# ig-normal2ver2.net
KiCad netlist of a schematic drawn in EAGLE
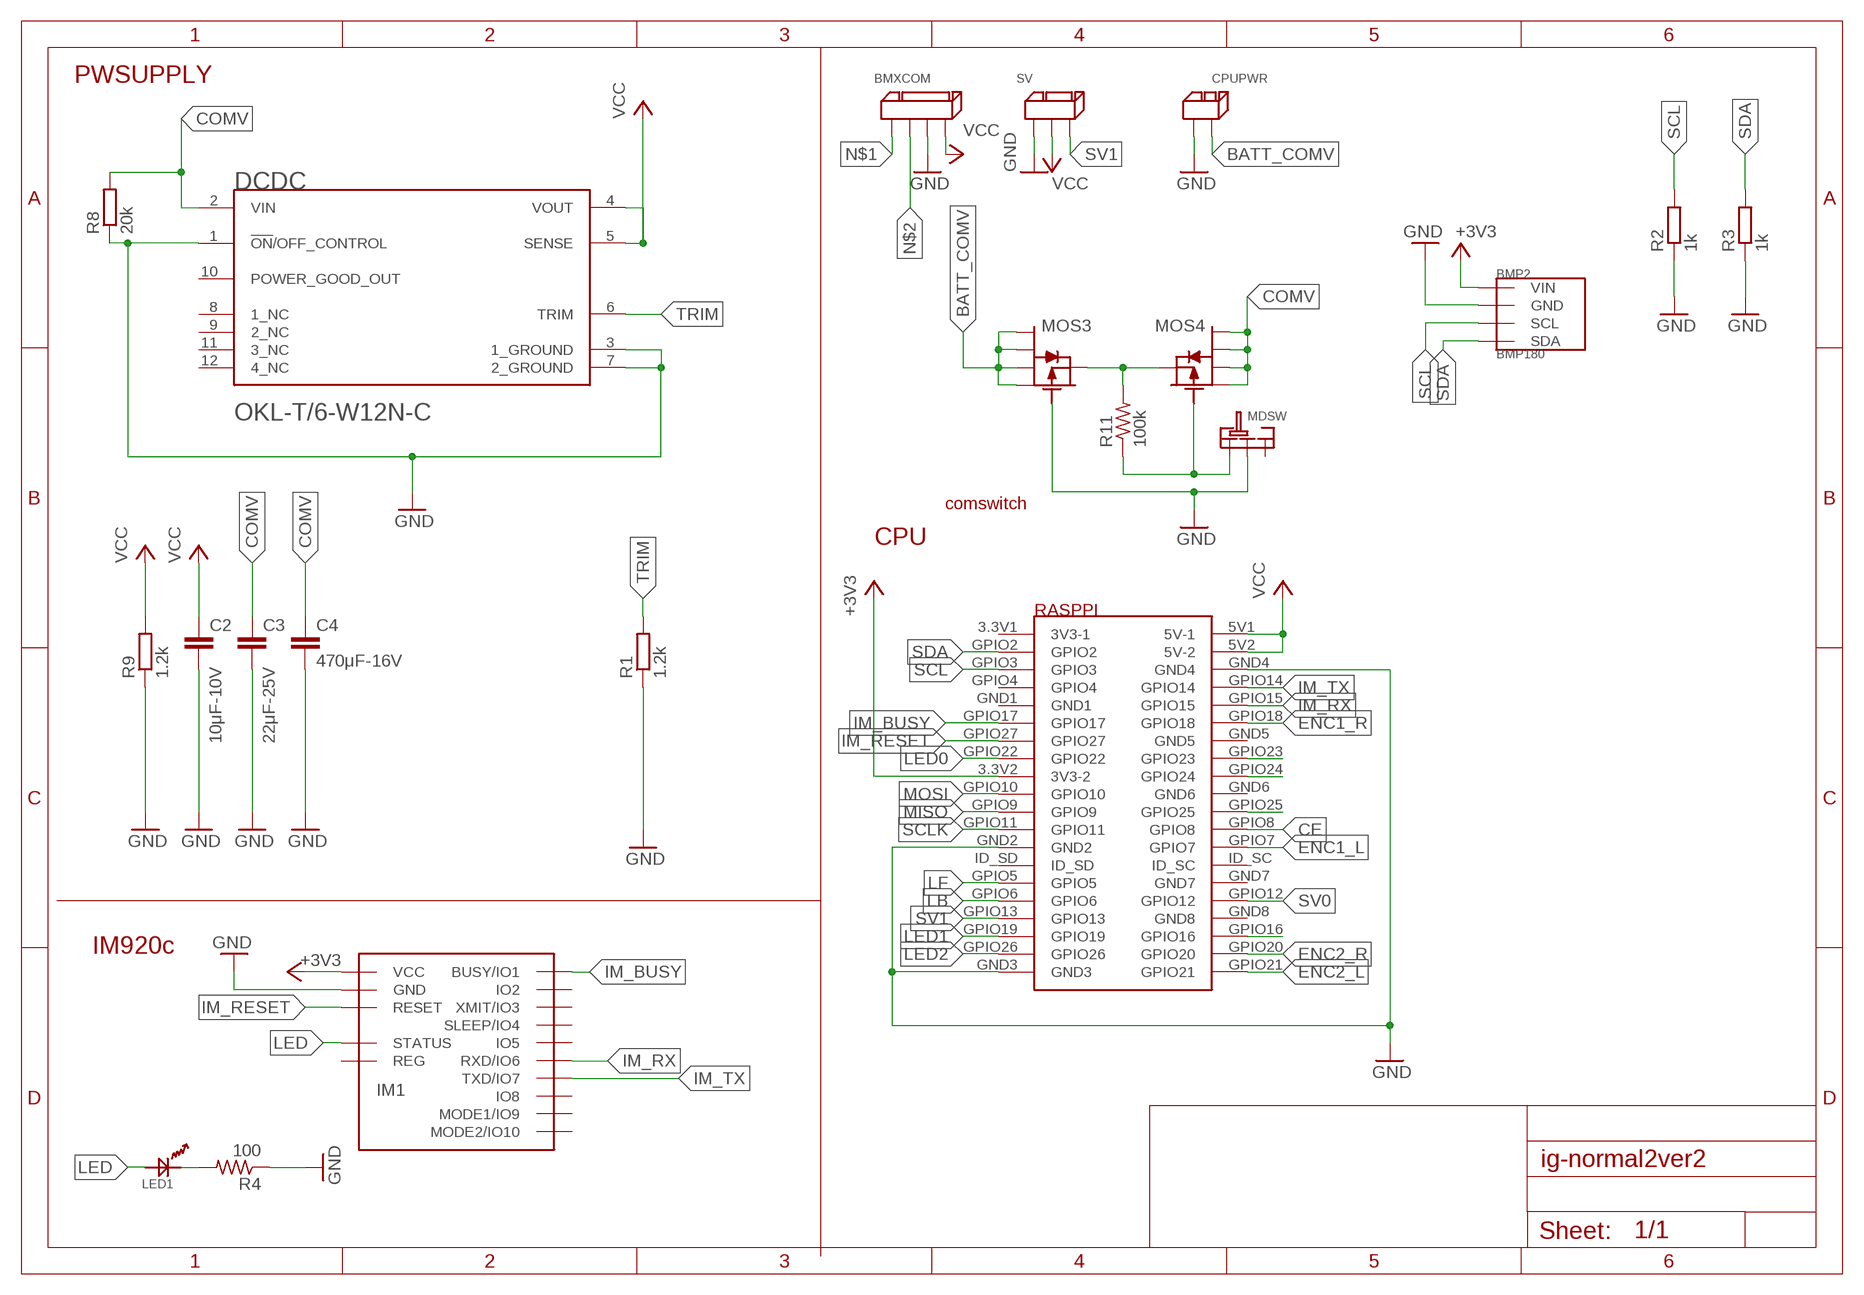
[diagram p0: schematic, sheet 1]

(export (version "E")
  (design (tool "Eeschema 10.0.6"))
  (components
    (comp (ref "BMP2")
      (value "BMP180")
      (footprint "eagle-import:GY-68")
      (libsource (lib "eagle-import") (part "BMP180"))
    )
    (comp (ref "BMXCOM")
      (value "4PIN")
      (footprint "eagle-import:4PIN")
      (libsource (lib "eagle-import") (part "4PIN"))
    )
    (comp (ref "C2")
      (value "10μF-10V")
      (footprint "eagle-import:C0603")
      (libsource (lib "eagle-import") (part "C-EUC0603"))
    )
    (comp (ref "C3")
      (value "22μF-25V")
      (footprint "eagle-import:C0603")
      (libsource (lib "eagle-import") (part "C-EUC0603"))
    )
    (comp (ref "C4")
      (value "470μF-16V")
      (footprint "eagle-import:C0603")
      (libsource (lib "eagle-import") (part "C-EUC0603"))
    )
    (comp (ref "CPUPWR")
      (value "2PIN")
      (footprint "eagle-import:2PIN")
      (libsource (lib "eagle-import") (part "2PIN"))
    )
    (comp (ref "DCDC")
      (value "OKL-T/6-W12N-CMURATA_OKL-T-6-W12N-C_0_0")
      (footprint "eagle-import:MURATA_OKL-T-6-W12N-C_0")
      (fields
        (field (name "DIGIKEY_PART_NUMBER") "811-2214-1-ND")
        (field (name "MF") "Murata")
        (field (name "MOUSER_PART_NUMBER") "580-OKL-T/6-W12N-C")
      )
      (libsource (lib "eagle-import") (part "OKL-T/6-W12N-CMURATA_OKL-T-6-W12N-C_0_0"))
    )
    (comp (ref "IM1")
      (value "IM920_IM920C")
      (footprint "eagle-import:IM920_IM920C")
      (libsource (lib "eagle-import") (part "IM920_IM920C"))
    )
    (comp (ref "LED1")
      (value "OSXX1608C1A")
      (footprint "eagle-import:OSXX1608C1A")
      (libsource (lib "eagle-import") (part "OSXX1608C1A"))
    )
    (comp (ref "MDSW")
      (value "SRIDE_SWITCH")
      (footprint "eagle-import:SRIDE_SWITCH")
      (libsource (lib "eagle-import") (part "SRIDE_SWITCH"))
    )
    (comp (ref "MOS3")
      (value "PCH_SSM6J808R")
      (footprint "eagle-import:SSM6J808R")
      (libsource (lib "eagle-import") (part "PCH_SSM6J808R"))
    )
    (comp (ref "MOS4")
      (value "PCH_SSM6J808R")
      (footprint "eagle-import:SSM6J808R")
      (libsource (lib "eagle-import") (part "PCH_SSM6J808R"))
    )
    (comp (ref "R1")
      (value "1.2k")
      (footprint "eagle-import:R0805")
      (libsource (lib "eagle-import") (part "R-EU_R0805"))
    )
    (comp (ref "R2")
      (value "1k")
      (footprint "eagle-import:R0603")
      (libsource (lib "eagle-import") (part "R-EU_R0603"))
    )
    (comp (ref "R3")
      (value "1k")
      (footprint "eagle-import:R0603")
      (libsource (lib "eagle-import") (part "R-EU_R0603"))
    )
    (comp (ref "R4")
      (value "100")
      (footprint "eagle-import:R0603")
      (libsource (lib "eagle-import") (part "R-US_R0603"))
    )
    (comp (ref "R8")
      (value "20k")
      (footprint "eagle-import:R0603")
      (libsource (lib "eagle-import") (part "R-EU_R0603"))
    )
    (comp (ref "R9")
      (value "1.2k")
      (footprint "eagle-import:R0805")
      (libsource (lib "eagle-import") (part "R-EU_R0805"))
    )
    (comp (ref "R11")
      (value "100k")
      (footprint "eagle-import:R0603")
      (libsource (lib "eagle-import") (part "R-US_R0603"))
    )
    (comp (ref "RASPPI")
      (value "RASPBERYPIZEROW")
      (footprint "eagle-import:RASPBERYPIZEROW")
      (libsource (lib "eagle-import") (part "RASPBERYPIZEROW"))
    )
    (comp (ref "SV")
      (value "3PIN")
      (footprint "eagle-import:3PIN")
      (libsource (lib "eagle-import") (part "3PIN"))
    )
  )
  (nets
    (net (code "1") (name "+3V3") (class "Default")
      (node (ref "BMP2") (pin "P1") (pinfunction "VIN_P1") (pintype "bidirectional"))
      (node (ref "IM1") (pin "$P17") (pinfunction "VCC_$P17") (pintype "bidirectional"))
      (node (ref "RASPPI") (pin "3.3V2") (pinfunction "3V3-2_3.3V2") (pintype "bidirectional"))
    )
    (net (code "2") (name "BATT_COMV") (class "Default")
      (node (ref "CPUPWR") (pin "P$2") (pinfunction "P$2_P$2") (pintype "bidirectional"))
      (node (ref "MOS3") (pin "1") (pinfunction "1_1") (pintype "bidirectional"))
      (node (ref "MOS3") (pin "2") (pinfunction "2_2") (pintype "bidirectional"))
      (node (ref "MOS3") (pin "5") (pinfunction "5_5") (pintype "bidirectional"))
      (node (ref "MOS3") (pin "6") (pinfunction "6_6") (pintype "bidirectional"))
    )
    (net (code "3") (name "CE") (class "Default")
      (node (ref "RASPPI") (pin "GPIO8") (pinfunction "GPIO8_GPIO8") (pintype "bidirectional"))
    )
    (net (code "4") (name "COMV") (class "Default")
      (node (ref "C3") (pin "1") (pinfunction "1_1") (pintype "passive"))
      (node (ref "C4") (pin "1") (pinfunction "1_1") (pintype "passive"))
      (node (ref "DCDC") (pin "2") (pinfunction "VIN_2") (pintype "bidirectional"))
      (node (ref "MOS4") (pin "1") (pinfunction "1_1") (pintype "bidirectional"))
      (node (ref "MOS4") (pin "2") (pinfunction "2_2") (pintype "bidirectional"))
      (node (ref "MOS4") (pin "5") (pinfunction "5_5") (pintype "bidirectional"))
      (node (ref "MOS4") (pin "6") (pinfunction "6_6") (pintype "bidirectional"))
      (node (ref "R8") (pin "2") (pinfunction "2_2") (pintype "passive"))
    )
    (net (code "5") (name "ENC1_L") (class "Default")
      (node (ref "RASPPI") (pin "GPIO7") (pinfunction "GPIO7_GPIO7") (pintype "bidirectional"))
    )
    (net (code "6") (name "ENC1_R") (class "Default")
      (node (ref "RASPPI") (pin "GPIO18") (pinfunction "GPIO18_GPIO18") (pintype "bidirectional"))
    )
    (net (code "7") (name "ENC2_L") (class "Default")
      (node (ref "RASPPI") (pin "GPIO21") (pinfunction "GPIO21_GPIO21") (pintype "bidirectional"))
    )
    (net (code "8") (name "ENC2_R") (class "Default")
      (node (ref "RASPPI") (pin "GPIO20") (pinfunction "GPIO20_GPIO20") (pintype "bidirectional"))
    )
    (net (code "9") (name "GND") (class "Default")
      (node (ref "BMP2") (pin "P2") (pinfunction "GND_P2") (pintype "bidirectional"))
      (node (ref "BMXCOM") (pin "P$3") (pinfunction "P$3_P$3") (pintype "bidirectional"))
      (node (ref "C2") (pin "2") (pinfunction "2_2") (pintype "passive"))
      (node (ref "C3") (pin "2") (pinfunction "2_2") (pintype "passive"))
      (node (ref "C4") (pin "2") (pinfunction "2_2") (pintype "passive"))
      (node (ref "CPUPWR") (pin "P$1") (pinfunction "P$1_P$1") (pintype "bidirectional"))
      (node (ref "DCDC") (pin "1") (pinfunction "~{ON}/OFF_CONTROL_1") (pintype "bidirectional"))
      (node (ref "DCDC") (pin "3") (pinfunction "1_GROUND_3") (pintype "power_in"))
      (node (ref "DCDC") (pin "7") (pinfunction "2_GROUND_7") (pintype "power_in"))
      (node (ref "IM1") (pin "$P18") (pinfunction "GND_$P18") (pintype "bidirectional"))
      (node (ref "MDSW") (pin "LR") (pinfunction "LR_LR") (pintype "bidirectional"))
      (node (ref "MOS3") (pin "3") (pinfunction "3_3") (pintype "bidirectional"))
      (node (ref "R1") (pin "1") (pinfunction "1_1") (pintype "passive"))
      (node (ref "R2") (pin "1") (pinfunction "1_1") (pintype "passive"))
      (node (ref "R3") (pin "1") (pinfunction "1_1") (pintype "passive"))
      (node (ref "R4") (pin "1") (pinfunction "1_1") (pintype "passive"))
      (node (ref "R8") (pin "1") (pinfunction "1_1") (pintype "passive"))
      (node (ref "R9") (pin "1") (pinfunction "1_1") (pintype "passive"))
      (node (ref "RASPPI") (pin "GND2") (pinfunction "GND2_GND2") (pintype "bidirectional"))
      (node (ref "RASPPI") (pin "GND3") (pinfunction "GND3_GND3") (pintype "bidirectional"))
      (node (ref "RASPPI") (pin "GND4") (pinfunction "GND4_GND4") (pintype "bidirectional"))
      (node (ref "SV") (pin "P$1") (pinfunction "P$1_P$1") (pintype "bidirectional"))
    )
    (net (code "10") (name "IM_BUSY") (class "Default")
      (node (ref "IM1") (pin "$P1") (pinfunction "BUSY/IO1_$P1") (pintype "bidirectional"))
      (node (ref "RASPPI") (pin "GPIO17") (pinfunction "GPIO17_GPIO17") (pintype "bidirectional"))
    )
    (net (code "11") (name "IM_RESET") (class "Default")
      (node (ref "IM1") (pin "$P19") (pinfunction "RESET_$P19") (pintype "bidirectional"))
      (node (ref "RASPPI") (pin "GPIO27") (pinfunction "GPIO27_GPIO27") (pintype "bidirectional"))
    )
    (net (code "12") (name "IM_RX") (class "Default")
      (node (ref "IM1") (pin "$P6") (pinfunction "RXD/IO6_$P6") (pintype "bidirectional"))
      (node (ref "RASPPI") (pin "GPIO15") (pinfunction "GPIO15_GPIO15") (pintype "bidirectional"))
    )
    (net (code "13") (name "IM_TX") (class "Default")
      (node (ref "IM1") (pin "$P7") (pinfunction "TXD/IO7_$P7") (pintype "bidirectional"))
      (node (ref "RASPPI") (pin "GPIO14") (pinfunction "GPIO14_GPIO14") (pintype "bidirectional"))
    )
    (net (code "14") (name "LB") (class "Default")
      (node (ref "RASPPI") (pin "GPIO6") (pinfunction "GPIO6_GPIO6") (pintype "bidirectional"))
    )
    (net (code "15") (name "LED") (class "Default")
      (node (ref "IM1") (pin "$P15") (pinfunction "STATUS_$P15") (pintype "bidirectional"))
      (node (ref "LED1") (pin "AN") (pinfunction "AN_AN") (pintype "bidirectional"))
    )
    (net (code "16") (name "LED0") (class "Default")
      (node (ref "RASPPI") (pin "GPIO22") (pinfunction "GPIO22_GPIO22") (pintype "bidirectional"))
    )
    (net (code "17") (name "LED1") (class "Default")
      (node (ref "RASPPI") (pin "GPIO19") (pinfunction "GPIO19_GPIO19") (pintype "bidirectional"))
    )
    (net (code "18") (name "LED2") (class "Default")
      (node (ref "RASPPI") (pin "GPIO26") (pinfunction "GPIO26_GPIO26") (pintype "bidirectional"))
    )
    (net (code "19") (name "LF") (class "Default")
      (node (ref "RASPPI") (pin "GPIO5") (pinfunction "GPIO5_GPIO5") (pintype "bidirectional"))
    )
    (net (code "20") (name "MISO") (class "Default")
      (node (ref "RASPPI") (pin "GPIO9") (pinfunction "GPIO9_GPIO9") (pintype "bidirectional"))
    )
    (net (code "21") (name "MOSI") (class "Default")
      (node (ref "RASPPI") (pin "GPIO10") (pinfunction "GPIO10_GPIO10") (pintype "bidirectional"))
    )
    (net (code "22") (name "N$1") (class "Default")
      (node (ref "BMXCOM") (pin "P$1") (pinfunction "P$1_P$1") (pintype "bidirectional"))
    )
    (net (code "23") (name "N$2") (class "Default")
      (node (ref "BMXCOM") (pin "P$2") (pinfunction "P$2_P$2") (pintype "bidirectional"))
    )
    (net (code "24") (name "Net-(LED1-PadCT)") (class "Default")
      (node (ref "LED1") (pin "CT") (pinfunction "CT_CT") (pintype "bidirectional"))
      (node (ref "R4") (pin "2") (pinfunction "2_2") (pintype "passive"))
    )
    (net (code "25") (name "Net-(MDSW-PadL)") (class "Default")
      (node (ref "MDSW") (pin "L") (pinfunction "L_L") (pintype "bidirectional"))
      (node (ref "MOS4") (pin "3") (pinfunction "3_3") (pintype "bidirectional"))
      (node (ref "R11") (pin "1") (pinfunction "1_1") (pintype "passive"))
    )
    (net (code "26") (name "Net-(MOS3-Pad4)") (class "Default")
      (node (ref "MOS3") (pin "4") (pinfunction "4_4") (pintype "bidirectional"))
      (node (ref "MOS4") (pin "4") (pinfunction "4_4") (pintype "bidirectional"))
      (node (ref "R11") (pin "2") (pinfunction "2_2") (pintype "passive"))
    )
    (net (code "27") (name "SCL") (class "Default")
      (node (ref "BMP2") (pin "P3") (pinfunction "SCL_P3") (pintype "bidirectional"))
      (node (ref "R2") (pin "2") (pinfunction "2_2") (pintype "passive"))
      (node (ref "RASPPI") (pin "GPIO3") (pinfunction "GPIO3_GPIO3") (pintype "bidirectional"))
    )
    (net (code "28") (name "SCLK") (class "Default")
      (node (ref "RASPPI") (pin "GPIO11") (pinfunction "GPIO11_GPIO11") (pintype "bidirectional"))
    )
    (net (code "29") (name "SDA") (class "Default")
      (node (ref "BMP2") (pin "P4") (pinfunction "SDA_P4") (pintype "bidirectional"))
      (node (ref "R3") (pin "2") (pinfunction "2_2") (pintype "passive"))
      (node (ref "RASPPI") (pin "GPIO2") (pinfunction "GPIO2_GPIO2") (pintype "bidirectional"))
    )
    (net (code "30") (name "SV0") (class "Default")
      (node (ref "RASPPI") (pin "GPIO12") (pinfunction "GPIO12_GPIO12") (pintype "bidirectional"))
    )
    (net (code "31") (name "SV1") (class "Default")
      (node (ref "RASPPI") (pin "GPIO13") (pinfunction "GPIO13_GPIO13") (pintype "bidirectional"))
      (node (ref "SV") (pin "P$3") (pinfunction "P$3_P$3") (pintype "bidirectional"))
    )
    (net (code "32") (name "TRIM") (class "Default")
      (node (ref "DCDC") (pin "6") (pinfunction "TRIM_6") (pintype "passive"))
      (node (ref "R1") (pin "2") (pinfunction "2_2") (pintype "passive"))
    )
    (net (code "33") (name "VCC") (class "Default")
      (node (ref "BMXCOM") (pin "P$4") (pinfunction "P$4_P$4") (pintype "bidirectional"))
      (node (ref "C2") (pin "1") (pinfunction "1_1") (pintype "passive"))
      (node (ref "DCDC") (pin "4") (pinfunction "VOUT_4") (pintype "bidirectional"))
      (node (ref "DCDC") (pin "5") (pinfunction "SENSE_5") (pintype "passive"))
      (node (ref "R9") (pin "2") (pinfunction "2_2") (pintype "passive"))
      (node (ref "RASPPI") (pin "5V1") (pinfunction "5V-1_5V1") (pintype "bidirectional"))
      (node (ref "RASPPI") (pin "5V2") (pinfunction "5V-2_5V2") (pintype "bidirectional"))
      (node (ref "SV") (pin "P$2") (pinfunction "P$2_P$2") (pintype "bidirectional"))
    )
    (net (code "34") (name "unconnected-(DCDC-1_NC-Pad8)") (class "Default")
      (node (ref "DCDC") (pin "8") (pinfunction "1_NC_8") (pintype "passive"))
    )
    (net (code "35") (name "unconnected-(DCDC-2_NC-Pad9)") (class "Default")
      (node (ref "DCDC") (pin "9") (pinfunction "2_NC_9") (pintype "passive"))
    )
    (net (code "36") (name "unconnected-(DCDC-3_NC-Pad11)") (class "Default")
      (node (ref "DCDC") (pin "11") (pinfunction "3_NC_11") (pintype "passive"))
    )
    (net (code "37") (name "unconnected-(DCDC-4_NC-Pad12)") (class "Default")
      (node (ref "DCDC") (pin "12") (pinfunction "4_NC_12") (pintype "passive"))
    )
    (net (code "38") (name "unconnected-(DCDC-POWER_GOOD_OUT-Pad10)") (class "Default")
      (node (ref "DCDC") (pin "10") (pinfunction "POWER_GOOD_OUT_10") (pintype "open_collector"))
    )
    (net (code "39") (name "unconnected-(IM1-IO2-Pad$P2)") (class "Default")
      (node (ref "IM1") (pin "$P2") (pinfunction "IO2_$P2") (pintype "bidirectional"))
    )
    (net (code "40") (name "unconnected-(IM1-IO5-Pad$P5)") (class "Default")
      (node (ref "IM1") (pin "$P5") (pinfunction "IO5_$P5") (pintype "bidirectional"))
    )
    (net (code "41") (name "unconnected-(IM1-IO8-Pad$P8)") (class "Default")
      (node (ref "IM1") (pin "$P8") (pinfunction "IO8_$P8") (pintype "bidirectional"))
    )
    (net (code "42") (name "unconnected-(IM1-MODE1{slash}IO9-Pad$P9)") (class "Default")
      (node (ref "IM1") (pin "$P9") (pinfunction "MODE1/IO9_$P9") (pintype "bidirectional"))
    )
    (net (code "43") (name "unconnected-(IM1-MODE2{slash}IO10-Pad$P10)") (class "Default")
      (node (ref "IM1") (pin "$P10") (pinfunction "MODE2/IO10_$P10") (pintype "bidirectional"))
    )
    (net (code "44") (name "unconnected-(IM1-REG-Pad$P16)") (class "Default")
      (node (ref "IM1") (pin "$P16") (pinfunction "REG_$P16") (pintype "bidirectional"))
    )
    (net (code "45") (name "unconnected-(IM1-SLEEP{slash}IO4-Pad$P4)") (class "Default")
      (node (ref "IM1") (pin "$P4") (pinfunction "SLEEP/IO4_$P4") (pintype "bidirectional"))
    )
    (net (code "46") (name "unconnected-(IM1-XMIT{slash}IO3-Pad$P3)") (class "Default")
      (node (ref "IM1") (pin "$P3") (pinfunction "XMIT/IO3_$P3") (pintype "bidirectional"))
    )
    (net (code "47") (name "unconnected-(MDSW-PadR)") (class "Default")
      (node (ref "MDSW") (pin "R") (pinfunction "R_R") (pintype "bidirectional"))
    )
    (net (code "48") (name "unconnected-(RASPPI-3V3-1-Pad3.3V1)") (class "Default")
      (node (ref "RASPPI") (pin "3.3V1") (pinfunction "3V3-1_3.3V1") (pintype "bidirectional"))
    )
    (net (code "49") (name "unconnected-(RASPPI-PadGND1)") (class "Default")
      (node (ref "RASPPI") (pin "GND1") (pinfunction "GND1_GND1") (pintype "bidirectional"))
    )
    (net (code "50") (name "unconnected-(RASPPI-PadGND5)") (class "Default")
      (node (ref "RASPPI") (pin "GND5") (pinfunction "GND5_GND5") (pintype "bidirectional"))
    )
    (net (code "51") (name "unconnected-(RASPPI-PadGND6)") (class "Default")
      (node (ref "RASPPI") (pin "GND6") (pinfunction "GND6_GND6") (pintype "bidirectional"))
    )
    (net (code "52") (name "unconnected-(RASPPI-PadGND7)") (class "Default")
      (node (ref "RASPPI") (pin "GND7") (pinfunction "GND7_GND7") (pintype "bidirectional"))
    )
    (net (code "53") (name "unconnected-(RASPPI-PadGND8)") (class "Default")
      (node (ref "RASPPI") (pin "GND8") (pinfunction "GND8_GND8") (pintype "bidirectional"))
    )
    (net (code "54") (name "unconnected-(RASPPI-PadGPIO4)") (class "Default")
      (node (ref "RASPPI") (pin "GPIO4") (pinfunction "GPIO4_GPIO4") (pintype "bidirectional"))
    )
    (net (code "55") (name "unconnected-(RASPPI-PadGPIO16)") (class "Default")
      (node (ref "RASPPI") (pin "GPIO16") (pinfunction "GPIO16_GPIO16") (pintype "bidirectional"))
    )
    (net (code "56") (name "unconnected-(RASPPI-PadGPIO23)") (class "Default")
      (node (ref "RASPPI") (pin "GPIO23") (pinfunction "GPIO23_GPIO23") (pintype "bidirectional"))
    )
    (net (code "57") (name "unconnected-(RASPPI-PadGPIO24)") (class "Default")
      (node (ref "RASPPI") (pin "GPIO24") (pinfunction "GPIO24_GPIO24") (pintype "bidirectional"))
    )
    (net (code "58") (name "unconnected-(RASPPI-PadGPIO25)") (class "Default")
      (node (ref "RASPPI") (pin "GPIO25") (pinfunction "GPIO25_GPIO25") (pintype "bidirectional"))
    )
    (net (code "59") (name "unconnected-(RASPPI-PadID_SC)") (class "Default")
      (node (ref "RASPPI") (pin "ID_SC") (pinfunction "ID_SC_ID_SC") (pintype "bidirectional"))
    )
    (net (code "60") (name "unconnected-(RASPPI-PadID_SD)") (class "Default")
      (node (ref "RASPPI") (pin "ID_SD") (pinfunction "ID_SD_ID_SD") (pintype "bidirectional"))
    )
  )
)
